# ECU_ADC.net
KiCad netlist of a schematic drawn in Altium Designer
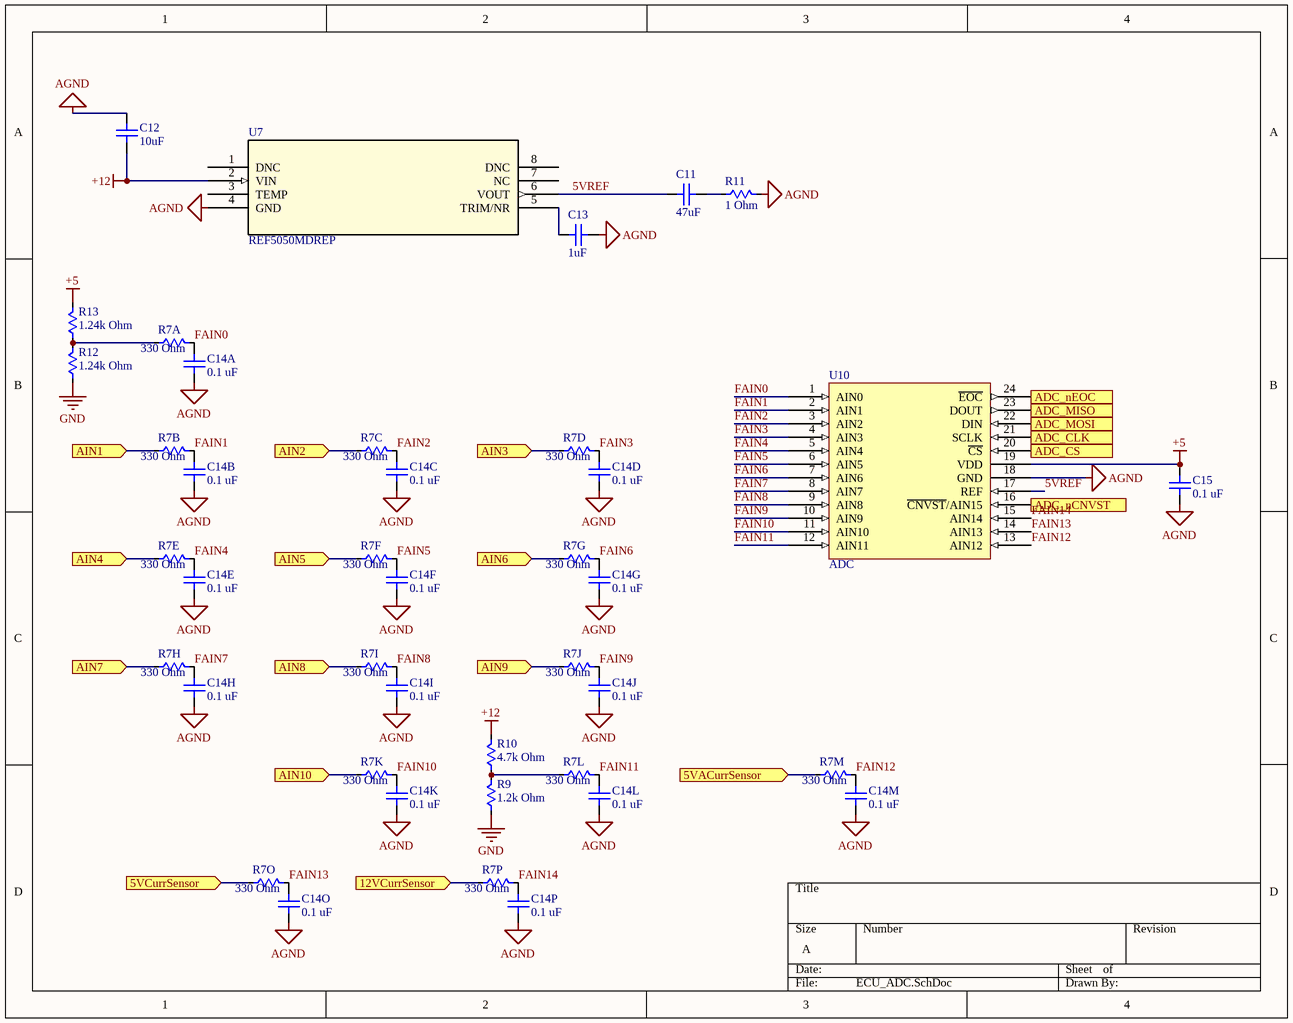
[diagram p0: ECU_ADC.SchDoc]

(export (version "E")
  (design (tool "Eeschema 10.0.6"))
  (components
    (comp (ref "C11")
      (value "47uF")
      (footprint "0805")
      (description "Samsung Microelectronics CL21A476MQYNNNE")
      (libsource (lib "Caps") (part "Cap_0805"))
    )
    (comp (ref "C12")
      (value "10uF")
      (footprint "0805")
      (description "Cap 0805")
      (libsource (lib "Caps") (part "Cap_0805"))
    )
    (comp (ref "C13")
      (value "1uF")
      (footprint "0805")
      (description "1uF Cap")
      (libsource (lib "Caps") (part "Cap_0805"))
    )
    (comp (ref "C14A")
      (value "0.1 uF")
      (footprint "0805")
      (description "Cap 0805")
      (libsource (lib "Caps") (part "Cap_0805"))
    )
    (comp (ref "C14B")
      (value "0.1 uF")
      (footprint "0805")
      (description "Cap 0805")
      (libsource (lib "Caps") (part "Cap_0805"))
    )
    (comp (ref "C14C")
      (value "0.1 uF")
      (footprint "0805")
      (description "Cap 0805")
      (libsource (lib "Caps") (part "Cap_0805"))
    )
    (comp (ref "C14D")
      (value "0.1 uF")
      (footprint "0805")
      (description "Cap 0805")
      (libsource (lib "Caps") (part "Cap_0805"))
    )
    (comp (ref "C14E")
      (value "0.1 uF")
      (footprint "0805")
      (description "Cap 0805")
      (libsource (lib "Caps") (part "Cap_0805"))
    )
    (comp (ref "C14F")
      (value "0.1 uF")
      (footprint "0805")
      (description "Cap 0805")
      (libsource (lib "Caps") (part "Cap_0805"))
    )
    (comp (ref "C14G")
      (value "0.1 uF")
      (footprint "0805")
      (description "Cap 0805")
      (libsource (lib "Caps") (part "Cap_0805"))
    )
    (comp (ref "C14H")
      (value "0.1 uF")
      (footprint "0805")
      (description "Cap 0805")
      (libsource (lib "Caps") (part "Cap_0805"))
    )
    (comp (ref "C14I")
      (value "0.1 uF")
      (footprint "0805")
      (description "Cap 0805")
      (libsource (lib "Caps") (part "Cap_0805"))
    )
    (comp (ref "C14J")
      (value "0.1 uF")
      (footprint "0805")
      (description "Cap 0805")
      (libsource (lib "Caps") (part "Cap_0805"))
    )
    (comp (ref "C14K")
      (value "0.1 uF")
      (footprint "0805")
      (description "Cap 0805")
      (libsource (lib "Caps") (part "Cap_0805"))
    )
    (comp (ref "C14L")
      (value "0.1 uF")
      (footprint "0805")
      (description "Cap 0805")
      (libsource (lib "Caps") (part "Cap_0805"))
    )
    (comp (ref "C14M")
      (value "0.1 uF")
      (footprint "0805")
      (description "Cap 0805")
      (libsource (lib "Caps") (part "Cap_0805"))
    )
    (comp (ref "C14O")
      (value "0.1 uF")
      (footprint "0805")
      (description "Cap 0805")
      (libsource (lib "Caps") (part "Cap_0805"))
    )
    (comp (ref "C14P")
      (value "0.1 uF")
      (footprint "0805")
      (description "Cap 0805")
      (libsource (lib "Caps") (part "Cap_0805"))
    )
    (comp (ref "C15")
      (value "0.1 uF")
      (footprint "0805")
      (description "Cap 0805")
      (libsource (lib "Caps") (part "Cap_0805"))
    )
    (comp (ref "R7A")
      (value "330 Ohm")
      (footprint "0805")
      (description "Res 0805")
      (libsource (lib "Resistors") (part "Res_0805"))
    )
    (comp (ref "R7B")
      (value "330 Ohm")
      (footprint "0805")
      (description "Res 0805")
      (libsource (lib "Resistors") (part "Res_0805"))
    )
    (comp (ref "R7C")
      (value "330 Ohm")
      (footprint "0805")
      (description "Res 0805")
      (libsource (lib "Resistors") (part "Res_0805"))
    )
    (comp (ref "R7D")
      (value "330 Ohm")
      (footprint "0805")
      (description "Res 0805")
      (libsource (lib "Resistors") (part "Res_0805"))
    )
    (comp (ref "R7E")
      (value "330 Ohm")
      (footprint "0805")
      (description "Res 0805")
      (libsource (lib "Resistors") (part "Res_0805"))
    )
    (comp (ref "R7F")
      (value "330 Ohm")
      (footprint "0805")
      (description "Res 0805")
      (libsource (lib "Resistors") (part "Res_0805"))
    )
    (comp (ref "R7G")
      (value "330 Ohm")
      (footprint "0805")
      (description "Res 0805")
      (libsource (lib "Resistors") (part "Res_0805"))
    )
    (comp (ref "R7H")
      (value "330 Ohm")
      (footprint "0805")
      (description "Res 0805")
      (libsource (lib "Resistors") (part "Res_0805"))
    )
    (comp (ref "R7I")
      (value "330 Ohm")
      (footprint "0805")
      (description "Res 0805")
      (libsource (lib "Resistors") (part "Res_0805"))
    )
    (comp (ref "R7J")
      (value "330 Ohm")
      (footprint "0805")
      (description "Res 0805")
      (libsource (lib "Resistors") (part "Res_0805"))
    )
    (comp (ref "R7K")
      (value "330 Ohm")
      (footprint "0805")
      (description "Res 0805")
      (libsource (lib "Resistors") (part "Res_0805"))
    )
    (comp (ref "R7L")
      (value "330 Ohm")
      (footprint "0805")
      (description "Res 0805")
      (libsource (lib "Resistors") (part "Res_0805"))
    )
    (comp (ref "R7M")
      (value "330 Ohm")
      (footprint "0805")
      (description "Res 0805")
      (libsource (lib "Resistors") (part "Res_0805"))
    )
    (comp (ref "R7O")
      (value "330 Ohm")
      (footprint "0805")
      (description "Res 0805")
      (libsource (lib "Resistors") (part "Res_0805"))
    )
    (comp (ref "R7P")
      (value "330 Ohm")
      (footprint "0805")
      (description "Res 0805")
      (libsource (lib "Resistors") (part "Res_0805"))
    )
    (comp (ref "R9")
      (value "1.2k Ohm")
      (footprint "0805")
      (description "Res 0805")
      (libsource (lib "Resistors") (part "Res_0805"))
    )
    (comp (ref "R10")
      (value "4.7k Ohm")
      (footprint "0805")
      (description "Res 0805")
      (libsource (lib "Resistors") (part "Res_0805"))
    )
    (comp (ref "R11")
      (value "1 Ohm")
      (footprint "0805")
      (description "Res 0805")
      (libsource (lib "Resistors") (part "Res_0805"))
    )
    (comp (ref "R12")
      (value "1.24k Ohm")
      (footprint "0805")
      (description "Res 0805")
      (libsource (lib "Resistors") (part "Res_0805"))
    )
    (comp (ref "R13")
      (value "1.24k Ohm")
      (footprint "0805")
      (description "Res 0805")
      (libsource (lib "Resistors") (part "Res_0805"))
    )
    (comp (ref "U7")
      (value "REF5050MDREP")
      (footprint "D8")
      (description "No Description Available")
      (fields (field (name "COPYRIGHT") "Copyright (C) 2022 Ultra Librarian. All rights reserved."))
      (libsource (lib "REF5050MDREP") (part "REF5050MDREP"))
    )
    (comp (ref "U10")
      (value "ADC")
      (footprint "QSOP24")
      (description "GLOVE, POLYAMIDE, L/FREE, PU, SIZE 6 - More Details")
      (libsource (lib "MAX11624EEG+-ND") (part "MAX11624EEG+-ND"))
    )
  )
  (nets
    (net (code "1") (name "+5") (class "Default")
      (node (ref "C15") (pin "2") (pinfunction "2_2") (pintype "passive"))
      (node (ref "R13") (pin "2") (pinfunction "2_2") (pintype "passive"))
      (node (ref "U10") (pin "19") (pinfunction "VDD_19") (pintype "power_in"))
    )
    (net (code "2") (name "+12") (class "Default")
      (node (ref "C12") (pin "2") (pinfunction "2_2") (pintype "passive"))
      (node (ref "R10") (pin "2") (pinfunction "2_2") (pintype "passive"))
      (node (ref "U7") (pin "2") (pinfunction "VIN_2") (pintype "input"))
    )
    (net (code "3") (name "/5VACurrSensor") (class "Default")
      (node (ref "R7M") (pin "1") (pinfunction "1_1") (pintype "passive"))
    )
    (net (code "4") (name "/5VCurrSensor") (class "Default")
      (node (ref "R7O") (pin "1") (pinfunction "1_1") (pintype "passive"))
    )
    (net (code "5") (name "/5VREF") (class "Default")
      (node (ref "C11") (pin "1") (pinfunction "1_1") (pintype "passive"))
      (node (ref "U10") (pin "17") (pinfunction "REF_17") (pintype "input"))
      (node (ref "U7") (pin "6") (pinfunction "VOUT_6") (pintype "output"))
    )
    (net (code "6") (name "/12VCurrSensor") (class "Default")
      (node (ref "R7P") (pin "1") (pinfunction "1_1") (pintype "passive"))
    )
    (net (code "7") (name "/ADC_CLK") (class "Default")
      (node (ref "U10") (pin "21") (pinfunction "SCLK_21") (pintype "input"))
    )
    (net (code "8") (name "/ADC_CS") (class "Default")
      (node (ref "U10") (pin "20") (pinfunction "~{CS}_20") (pintype "input"))
    )
    (net (code "9") (name "/ADC_MISO") (class "Default")
      (node (ref "U10") (pin "23") (pinfunction "DOUT_23") (pintype "output"))
    )
    (net (code "10") (name "/ADC_MOSI") (class "Default")
      (node (ref "U10") (pin "22") (pinfunction "DIN_22") (pintype "input"))
    )
    (net (code "11") (name "/ADC_nCNVST") (class "Default")
      (node (ref "U10") (pin "16") (pinfunction "~{CNVST}/AIN15_16") (pintype "input"))
    )
    (net (code "12") (name "/ADC_nEOC") (class "Default")
      (node (ref "U10") (pin "24") (pinfunction "~{EOC}_24") (pintype "output"))
    )
    (net (code "13") (name "/AIN1") (class "Default")
      (node (ref "R7B") (pin "1") (pinfunction "1_1") (pintype "passive"))
    )
    (net (code "14") (name "/AIN2") (class "Default")
      (node (ref "R7C") (pin "1") (pinfunction "1_1") (pintype "passive"))
    )
    (net (code "15") (name "/AIN3") (class "Default")
      (node (ref "R7D") (pin "1") (pinfunction "1_1") (pintype "passive"))
    )
    (net (code "16") (name "/AIN4") (class "Default")
      (node (ref "R7E") (pin "1") (pinfunction "1_1") (pintype "passive"))
    )
    (net (code "17") (name "/AIN5") (class "Default")
      (node (ref "R7F") (pin "1") (pinfunction "1_1") (pintype "passive"))
    )
    (net (code "18") (name "/AIN6") (class "Default")
      (node (ref "R7G") (pin "1") (pinfunction "1_1") (pintype "passive"))
    )
    (net (code "19") (name "/AIN7") (class "Default")
      (node (ref "R7H") (pin "1") (pinfunction "1_1") (pintype "passive"))
    )
    (net (code "20") (name "/AIN8") (class "Default")
      (node (ref "R7I") (pin "1") (pinfunction "1_1") (pintype "passive"))
    )
    (net (code "21") (name "/AIN9") (class "Default")
      (node (ref "R7J") (pin "1") (pinfunction "1_1") (pintype "passive"))
    )
    (net (code "22") (name "/AIN10") (class "Default")
      (node (ref "R7K") (pin "1") (pinfunction "1_1") (pintype "passive"))
    )
    (net (code "23") (name "/FAIN0") (class "Default")
      (node (ref "C14A") (pin "2") (pinfunction "2_2") (pintype "passive"))
      (node (ref "R7A") (pin "2") (pinfunction "2_2") (pintype "passive"))
      (node (ref "U10") (pin "1") (pinfunction "AIN0_1") (pintype "input"))
    )
    (net (code "24") (name "/FAIN1") (class "Default")
      (node (ref "C14B") (pin "2") (pinfunction "2_2") (pintype "passive"))
      (node (ref "R7B") (pin "2") (pinfunction "2_2") (pintype "passive"))
      (node (ref "U10") (pin "2") (pinfunction "AIN1_2") (pintype "input"))
    )
    (net (code "25") (name "/FAIN2") (class "Default")
      (node (ref "C14C") (pin "2") (pinfunction "2_2") (pintype "passive"))
      (node (ref "R7C") (pin "2") (pinfunction "2_2") (pintype "passive"))
      (node (ref "U10") (pin "3") (pinfunction "AIN2_3") (pintype "input"))
    )
    (net (code "26") (name "/FAIN3") (class "Default")
      (node (ref "C14D") (pin "2") (pinfunction "2_2") (pintype "passive"))
      (node (ref "R7D") (pin "2") (pinfunction "2_2") (pintype "passive"))
      (node (ref "U10") (pin "4") (pinfunction "AIN3_4") (pintype "input"))
    )
    (net (code "27") (name "/FAIN4") (class "Default")
      (node (ref "C14E") (pin "2") (pinfunction "2_2") (pintype "passive"))
      (node (ref "R7E") (pin "2") (pinfunction "2_2") (pintype "passive"))
      (node (ref "U10") (pin "5") (pinfunction "AIN4_5") (pintype "input"))
    )
    (net (code "28") (name "/FAIN5") (class "Default")
      (node (ref "C14F") (pin "2") (pinfunction "2_2") (pintype "passive"))
      (node (ref "R7F") (pin "2") (pinfunction "2_2") (pintype "passive"))
      (node (ref "U10") (pin "6") (pinfunction "AIN5_6") (pintype "input"))
    )
    (net (code "29") (name "/FAIN6") (class "Default")
      (node (ref "C14G") (pin "2") (pinfunction "2_2") (pintype "passive"))
      (node (ref "R7G") (pin "2") (pinfunction "2_2") (pintype "passive"))
      (node (ref "U10") (pin "7") (pinfunction "AIN6_7") (pintype "input"))
    )
    (net (code "30") (name "/FAIN7") (class "Default")
      (node (ref "C14H") (pin "2") (pinfunction "2_2") (pintype "passive"))
      (node (ref "R7H") (pin "2") (pinfunction "2_2") (pintype "passive"))
      (node (ref "U10") (pin "8") (pinfunction "AIN7_8") (pintype "input"))
    )
    (net (code "31") (name "/FAIN8") (class "Default")
      (node (ref "C14I") (pin "2") (pinfunction "2_2") (pintype "passive"))
      (node (ref "R7I") (pin "2") (pinfunction "2_2") (pintype "passive"))
      (node (ref "U10") (pin "9") (pinfunction "AIN8_9") (pintype "input"))
    )
    (net (code "32") (name "/FAIN9") (class "Default")
      (node (ref "C14J") (pin "2") (pinfunction "2_2") (pintype "passive"))
      (node (ref "R7J") (pin "2") (pinfunction "2_2") (pintype "passive"))
      (node (ref "U10") (pin "10") (pinfunction "AIN9_10") (pintype "input"))
    )
    (net (code "33") (name "/FAIN10") (class "Default")
      (node (ref "C14K") (pin "2") (pinfunction "2_2") (pintype "passive"))
      (node (ref "R7K") (pin "2") (pinfunction "2_2") (pintype "passive"))
      (node (ref "U10") (pin "11") (pinfunction "AIN10_11") (pintype "input"))
    )
    (net (code "34") (name "/FAIN11") (class "Default")
      (node (ref "C14L") (pin "2") (pinfunction "2_2") (pintype "passive"))
      (node (ref "R7L") (pin "2") (pinfunction "2_2") (pintype "passive"))
      (node (ref "U10") (pin "12") (pinfunction "AIN11_12") (pintype "input"))
    )
    (net (code "35") (name "/FAIN12") (class "Default")
      (node (ref "C14M") (pin "2") (pinfunction "2_2") (pintype "passive"))
      (node (ref "R7M") (pin "2") (pinfunction "2_2") (pintype "passive"))
      (node (ref "U10") (pin "13") (pinfunction "AIN12_13") (pintype "input"))
    )
    (net (code "36") (name "/FAIN13") (class "Default")
      (node (ref "C14O") (pin "2") (pinfunction "2_2") (pintype "passive"))
      (node (ref "R7O") (pin "2") (pinfunction "2_2") (pintype "passive"))
      (node (ref "U10") (pin "14") (pinfunction "AIN13_14") (pintype "input"))
    )
    (net (code "37") (name "/FAIN14") (class "Default")
      (node (ref "C14P") (pin "2") (pinfunction "2_2") (pintype "passive"))
      (node (ref "R7P") (pin "2") (pinfunction "2_2") (pintype "passive"))
      (node (ref "U10") (pin "15") (pinfunction "AIN14_15") (pintype "input"))
    )
    (net (code "38") (name "AGND") (class "Default")
      (node (ref "C12") (pin "1") (pinfunction "1_1") (pintype "passive"))
      (node (ref "C13") (pin "2") (pinfunction "2_2") (pintype "passive"))
      (node (ref "C14A") (pin "1") (pinfunction "1_1") (pintype "passive"))
      (node (ref "C14B") (pin "1") (pinfunction "1_1") (pintype "passive"))
      (node (ref "C14C") (pin "1") (pinfunction "1_1") (pintype "passive"))
      (node (ref "C14D") (pin "1") (pinfunction "1_1") (pintype "passive"))
      (node (ref "C14E") (pin "1") (pinfunction "1_1") (pintype "passive"))
      (node (ref "C14F") (pin "1") (pinfunction "1_1") (pintype "passive"))
      (node (ref "C14G") (pin "1") (pinfunction "1_1") (pintype "passive"))
      (node (ref "C14H") (pin "1") (pinfunction "1_1") (pintype "passive"))
      (node (ref "C14I") (pin "1") (pinfunction "1_1") (pintype "passive"))
      (node (ref "C14J") (pin "1") (pinfunction "1_1") (pintype "passive"))
      (node (ref "C14K") (pin "1") (pinfunction "1_1") (pintype "passive"))
      (node (ref "C14L") (pin "1") (pinfunction "1_1") (pintype "passive"))
      (node (ref "C14M") (pin "1") (pinfunction "1_1") (pintype "passive"))
      (node (ref "C14O") (pin "1") (pinfunction "1_1") (pintype "passive"))
      (node (ref "C14P") (pin "1") (pinfunction "1_1") (pintype "passive"))
      (node (ref "C15") (pin "1") (pinfunction "1_1") (pintype "passive"))
      (node (ref "R11") (pin "2") (pinfunction "2_2") (pintype "passive"))
      (node (ref "U10") (pin "18") (pinfunction "GND_18") (pintype "power_in"))
      (node (ref "U7") (pin "4") (pinfunction "GND_4") (pintype "passive"))
    )
    (net (code "39") (name "GND") (class "Default")
      (node (ref "R12") (pin "1") (pinfunction "1_1") (pintype "passive"))
      (node (ref "R9") (pin "1") (pinfunction "1_1") (pintype "passive"))
    )
    (net (code "40") (name "Net-(C11-Pad2)") (class "Default")
      (node (ref "C11") (pin "2") (pinfunction "2_2") (pintype "passive"))
      (node (ref "R11") (pin "1") (pinfunction "1_1") (pintype "passive"))
    )
    (net (code "41") (name "Net-(R10-Pad1)") (class "Default")
      (node (ref "R10") (pin "1") (pinfunction "1_1") (pintype "passive"))
      (node (ref "R7L") (pin "1") (pinfunction "1_1") (pintype "passive"))
      (node (ref "R9") (pin "2") (pinfunction "2_2") (pintype "passive"))
    )
    (net (code "42") (name "Net-(R12-Pad2)") (class "Default")
      (node (ref "R12") (pin "2") (pinfunction "2_2") (pintype "passive"))
      (node (ref "R13") (pin "1") (pinfunction "1_1") (pintype "passive"))
      (node (ref "R7A") (pin "1") (pinfunction "1_1") (pintype "passive"))
    )
    (net (code "43") (name "Net-(U7-TRIM{slash}NR)") (class "Default")
      (node (ref "C13") (pin "1") (pinfunction "1_1") (pintype "passive"))
      (node (ref "U7") (pin "5") (pinfunction "TRIM/NR_5") (pintype "passive"))
    )
    (net (code "44") (name "unconnected-(U7-DNC-Pad1)") (class "Default")
      (node (ref "U7") (pin "1") (pinfunction "DNC_1") (pintype "passive"))
    )
    (net (code "45") (name "unconnected-(U7-DNC-Pad8)") (class "Default")
      (node (ref "U7") (pin "8") (pinfunction "DNC_8") (pintype "passive"))
    )
    (net (code "46") (name "unconnected-(U7-NC-Pad7)") (class "Default")
      (node (ref "U7") (pin "7") (pinfunction "NC_7") (pintype "passive"))
    )
    (net (code "47") (name "unconnected-(U7-TEMP-Pad3)") (class "Default")
      (node (ref "U7") (pin "3") (pinfunction "TEMP_3") (pintype "passive"))
    )
  )
)
